# GPS_LEA5S_v_0_1.net
KiCad netlist of a schematic drawn in Altium Designer
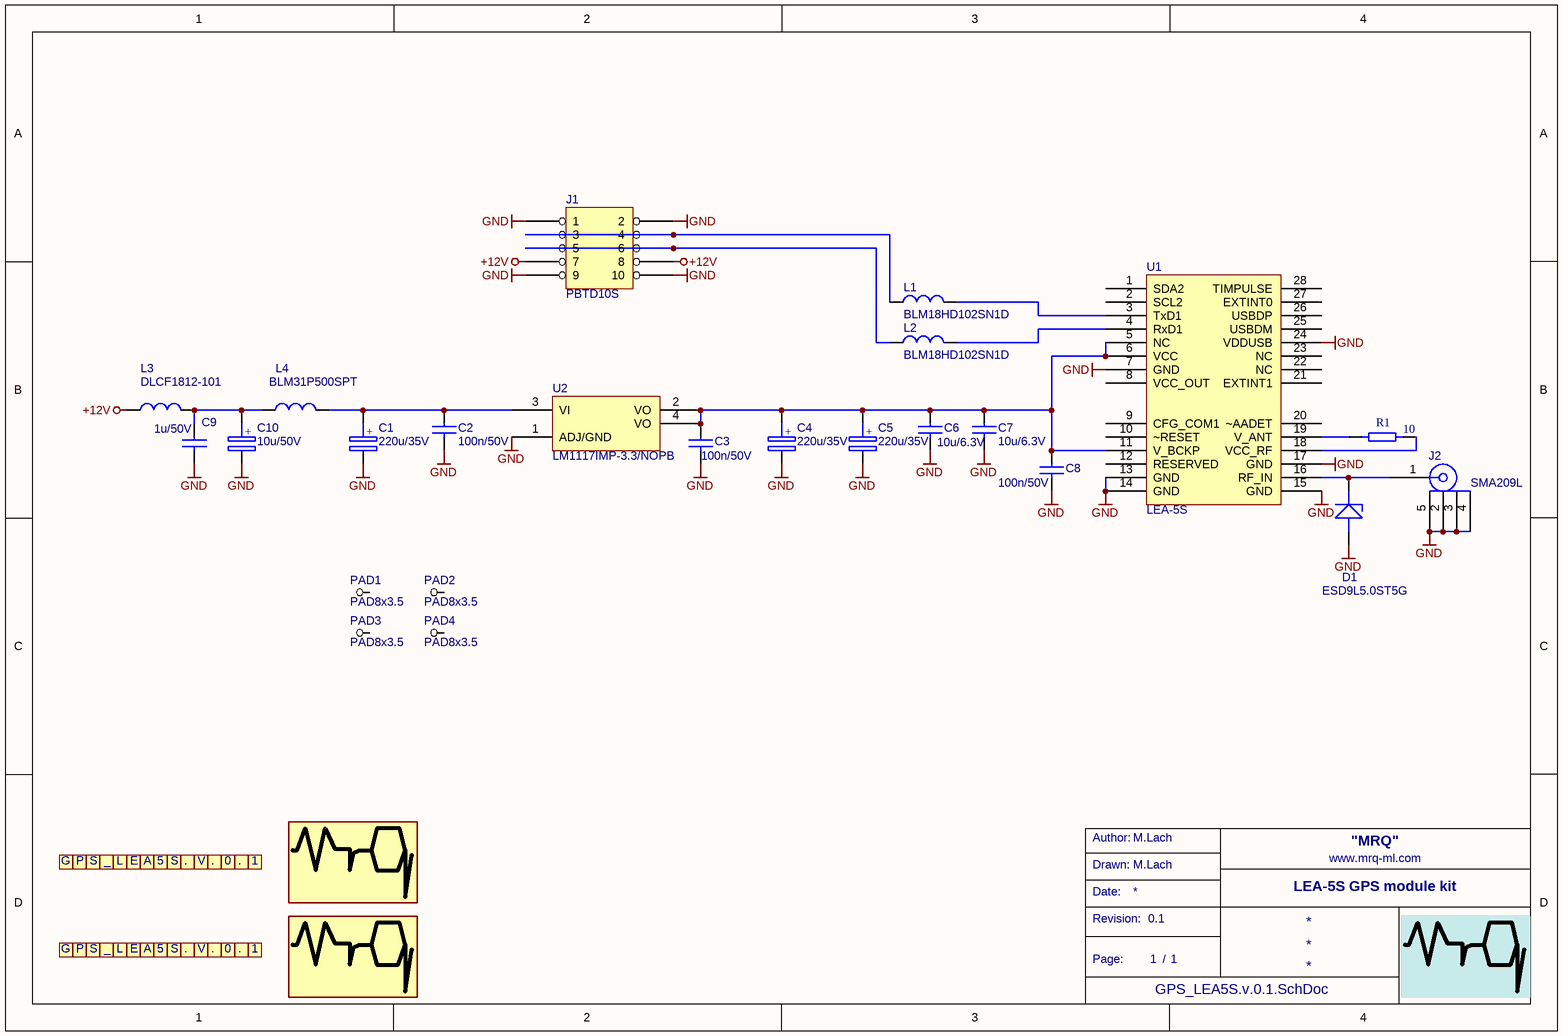
[diagram p0: GPS_LEA5S.v.0.1.SchDoc]

(export (version "E")
  (design (tool "Eeschema 10.0.6"))
  (components
    (comp (ref "C1")
      (value "220u/35V")
      (footprint "CELE")
      (fields (field (name "TOLERANCE") "20%"))
      (libsource (lib "Parts") (part "CEL"))
    )
    (comp (ref "C2")
      (value "100n/50V")
      (footprint "0805")
      (fields (field (name "TOLERANCE") "10%"))
      (libsource (lib "Parts") (part "C"))
    )
    (comp (ref "C3")
      (value "100n/50V")
      (footprint "0805")
      (fields (field (name "TOLERANCE") "10%"))
      (libsource (lib "Parts") (part "C"))
    )
    (comp (ref "C4")
      (value "220u/35V")
      (footprint "CELE")
      (fields (field (name "TOLERANCE") "20%"))
      (libsource (lib "Parts") (part "CEL"))
    )
    (comp (ref "C5")
      (value "220u/35V")
      (footprint "CELE")
      (fields (field (name "TOLERANCE") "20%"))
      (libsource (lib "Parts") (part "CEL"))
    )
    (comp (ref "C6")
      (value "10u/6.3V")
      (footprint "1206")
      (fields (field (name "TOLERANCE") "10%"))
      (libsource (lib "Parts") (part "C"))
    )
    (comp (ref "C7")
      (value "10u/6.3V")
      (footprint "1206")
      (fields (field (name "TOLERANCE") "10%"))
      (libsource (lib "Parts") (part "C"))
    )
    (comp (ref "C8")
      (value "100n/50V")
      (footprint "0805")
      (fields (field (name "TOLERANCE") "10%"))
      (libsource (lib "Parts") (part "C"))
    )
    (comp (ref "C9")
      (value "1u/50V")
      (footprint "1206")
      (fields (field (name "TOLERANCE") "10%"))
      (libsource (lib "Parts") (part "C"))
    )
    (comp (ref "C10")
      (value "10u/50V")
      (footprint "CE6.3x5.5")
      (fields (field (name "TOLERANCE") "20%"))
      (libsource (lib "Parts") (part "CEL"))
    )
    (comp (ref "D1")
      (value "ESD9L5.0ST5G")
      (footprint "SOD923")
      (libsource (lib "Parts") (part "DIODE BREAKDOWN"))
    )
    (comp (ref "J1")
      (value "PBTD10S")
      (footprint "PBTD10S")
      (description "Connector")
      (libsource (lib "Parts") (part "HEADER5X2"))
    )
    (comp (ref "J2") (value "SMA209L") (footprint "SMA209L") (libsource (lib "Parts") (part "SMA211L")))
    (comp (ref "L1") (value "BLM18HD102SN1D") (footprint "0603") (libsource (lib "Parts") (part "INDUCTOR")))
    (comp (ref "L2") (value "BLM18HD102SN1D") (footprint "0603") (libsource (lib "Parts") (part "INDUCTOR")))
    (comp (ref "L3") (value "DLCF1812-101") (footprint "1812") (libsource (lib "Parts") (part "INDUCTOR")))
    (comp (ref "L4") (value "BLM31P500SPT") (footprint "1206") (libsource (lib "Parts") (part "INDUCTOR")))
    (comp (ref "LETTER1")
      (value "LETTER_E")
      (footprint "LETTERC_E_60_10_TS")
      (libsource (lib "Schematic") (part "LETTER_E"))
    )
    (comp (ref "LETTER2")
      (value "LETTER_DOT")
      (footprint "LETTER_DOT_60_10_TS")
      (libsource (lib "Schematic") (part "LETTER_DOT"))
    )
    (comp (ref "LETTER3")
      (value "LETTER_G")
      (footprint "LETTERC_G_60_10_TS")
      (libsource (lib "Schematic") (part "LETTER_G"))
    )
    (comp (ref "LETTER4")
      (value "LETTER_DOT")
      (footprint "LETTER_DOT_60_10_TS")
      (libsource (lib "Schematic") (part "LETTER_DOT"))
    )
    (comp (ref "LETTER5")
      (value "LETTER_S")
      (footprint "LETTERC_S_60_10_TS")
      (libsource (lib "Schematic") (part "LETTER_S"))
    )
    (comp (ref "LETTER6")
      (value "LETTER_P")
      (footprint "LETTERC_P_60_10_TS")
      (libsource (lib "Schematic") (part "LETTER_P"))
    )
    (comp (ref "LETTER7")
      (value "LETTER_P")
      (footprint "LETTERC_L_60_10_TS")
      (libsource (lib "Schematic") (part "LETTER_L"))
    )
    (comp (ref "LETTER8")
      (value "LETTER_DOT")
      (footprint "LETTER_DOT_60_10_TS")
      (libsource (lib "Schematic") (part "LETTER_DOT"))
    )
    (comp (ref "LETTER9")
      (value "LETTER_1")
      (footprint "LETTER_1_60_10_TS")
      (libsource (lib "Schematic") (part "LETTER_1"))
    )
    (comp (ref "LETTER10")
      (value "LETTER_G")
      (footprint "LETTERC_G_60_10_TS")
      (libsource (lib "Schematic") (part "LETTER_G"))
    )
    (comp (ref "LETTER11")
      (value "LETTER_UNDERSCORE")
      (footprint "LETTER_UNDERSCORE_60_10_TS")
      (libsource (lib "Schematic") (part "LETTER_UNDERSCORE"))
    )
    (comp (ref "LETTER12")
      (value "LETTER_A_CAPITAL")
      (footprint "LETTERC_A_60_10_TS")
      (libsource (lib "Schematic") (part "LETTER_A"))
    )
    (comp (ref "LETTER13")
      (value "LETTER_5")
      (footprint "LETTER_5_60_10_TS")
      (libsource (lib "Schematic") (part "LETTER_5"))
    )
    (comp (ref "LETTER14")
      (value "LETTER_S")
      (footprint "LETTERC_S_60_10_TS")
      (libsource (lib "Schematic") (part "LETTER_S"))
    )
    (comp (ref "LETTER15")
      (value "LETTER_P")
      (footprint "LETTERC_P_60_10_TS")
      (libsource (lib "Schematic") (part "LETTER_P"))
    )
    (comp (ref "LETTER16")
      (value "LETTER_V")
      (footprint "LETTER_V_60_10_TS")
      (libsource (lib "Schematic") (part "LETTER_V"))
    )
    (comp (ref "LETTER17")
      (value "LETTER_S")
      (footprint "LETTERC_S_60_10_TS")
      (libsource (lib "Schematic") (part "LETTER_S"))
    )
    (comp (ref "LETTER18")
      (value "LETTER_0")
      (footprint "LETTER_0_60_10_TS")
      (libsource (lib "Schematic") (part "LETTER_0"))
    )
    (comp (ref "LETTER19")
      (value "LETTER_UNDERSCORE")
      (footprint "LETTER_UNDERSCORE_60_10_TS")
      (libsource (lib "Schematic") (part "LETTER_UNDERSCORE"))
    )
    (comp (ref "LETTER20")
      (value "LETTER_P")
      (footprint "LETTERC_L_60_10_TS")
      (libsource (lib "Schematic") (part "LETTER_L"))
    )
    (comp (ref "LETTER21")
      (value "LETTER_E")
      (footprint "LETTERC_E_60_10_TS")
      (libsource (lib "Schematic") (part "LETTER_E"))
    )
    (comp (ref "LETTER22")
      (value "LETTER_A_CAPITAL")
      (footprint "LETTERC_A_60_10_TS")
      (libsource (lib "Schematic") (part "LETTER_A"))
    )
    (comp (ref "LETTER23")
      (value "LETTER_5")
      (footprint "LETTER_5_60_10_TS")
      (libsource (lib "Schematic") (part "LETTER_5"))
    )
    (comp (ref "LETTER24")
      (value "LETTER_S")
      (footprint "LETTERC_S_60_10_TS")
      (libsource (lib "Schematic") (part "LETTER_S"))
    )
    (comp (ref "LETTER25")
      (value "LETTER_DOT")
      (footprint "LETTER_DOT_60_10_TS")
      (libsource (lib "Schematic") (part "LETTER_DOT"))
    )
    (comp (ref "LETTER26")
      (value "LETTER_V")
      (footprint "LETTER_V_60_10_TS")
      (libsource (lib "Schematic") (part "LETTER_V"))
    )
    (comp (ref "LETTER27")
      (value "LETTER_DOT")
      (footprint "LETTER_DOT_60_10_TS")
      (libsource (lib "Schematic") (part "LETTER_DOT"))
    )
    (comp (ref "LETTER28")
      (value "LETTER_0")
      (footprint "LETTER_0_60_10_TS")
      (libsource (lib "Schematic") (part "LETTER_0"))
    )
    (comp (ref "LETTER29")
      (value "LETTER_DOT")
      (footprint "LETTER_DOT_60_10_TS")
      (libsource (lib "Schematic") (part "LETTER_DOT"))
    )
    (comp (ref "LETTER30")
      (value "LETTER_1")
      (footprint "LETTER_1_60_10_TS")
      (libsource (lib "Schematic") (part "LETTER_1"))
    )
    (comp (ref "LOGO1")
      (value "MRQLOGO")
      (footprint "MRQ_5_TS")
      (libsource (lib "Schematic") (part "MRQLOGO"))
    )
    (comp (ref "LOGO3")
      (value "MRQLOGO")
      (footprint "MRQ_5_TS")
      (libsource (lib "Schematic") (part "MRQLOGO"))
    )
    (comp (ref "PAD1")
      (value "PAD8x3.5")
      (footprint "PAD8x3.5")
      (libsource (lib "Schematic") (part "PAD8x3.5"))
    )
    (comp (ref "PAD2")
      (value "PAD8x3.5")
      (footprint "PAD8x3.5")
      (libsource (lib "Schematic") (part "PAD8x3.5"))
    )
    (comp (ref "PAD3")
      (value "PAD8x3.5")
      (footprint "PAD8x3.5")
      (libsource (lib "Schematic") (part "PAD8x3.5"))
    )
    (comp (ref "PAD4")
      (value "PAD8x3.5")
      (footprint "PAD8x3.5")
      (libsource (lib "Schematic") (part "PAD8x3.5"))
    )
    (comp (ref "R1")
      (value "10")
      (footprint "0805")
      (fields (field (name "TOLERANCE") "5%"))
      (libsource (lib "Parts") (part "R"))
    )
    (comp (ref "TB") (value "TITLEBLOCK") (libsource (lib "Schematic") (part "TITLEBLOCK")))
    (comp (ref "U1") (value "LEA-5S") (footprint "LEA-LA") (libsource (lib "Parts") (part "LEA-5S")))
    (comp (ref "U2")
      (value "LM1117IMP-3.3/NOPB")
      (footprint "SOT-223")
      (libsource (lib "Parts") (part "LM1117IMP"))
    )
  )
  (nets
    (net (code "1") (name "+12V") (class "Default")
      (node (ref "J1") (pin "7") (pinfunction "7_7") (pintype "passive"))
      (node (ref "J1") (pin "8") (pinfunction "8_8") (pintype "passive"))
      (node (ref "L3") (pin "1") (pinfunction "1_1") (pintype "passive"))
    )
    (net (code "2") (name "GND") (class "Default")
      (node (ref "C1") (pin "1") (pinfunction "1_1") (pintype "passive"))
      (node (ref "C10") (pin "1") (pinfunction "1_1") (pintype "passive"))
      (node (ref "C2") (pin "2") (pinfunction "2_2") (pintype "passive"))
      (node (ref "C3") (pin "2") (pinfunction "2_2") (pintype "passive"))
      (node (ref "C4") (pin "1") (pinfunction "1_1") (pintype "passive"))
      (node (ref "C5") (pin "1") (pinfunction "1_1") (pintype "passive"))
      (node (ref "C6") (pin "2") (pinfunction "2_2") (pintype "passive"))
      (node (ref "C7") (pin "2") (pinfunction "2_2") (pintype "passive"))
      (node (ref "C8") (pin "2") (pinfunction "2_2") (pintype "passive"))
      (node (ref "C9") (pin "2") (pinfunction "2_2") (pintype "passive"))
      (node (ref "D1") (pin "ANOD") (pinfunction "ANOD_ANOD") (pintype "passive"))
      (node (ref "J1") (pin "1") (pinfunction "1_1") (pintype "passive"))
      (node (ref "J1") (pin "10") (pinfunction "10_10") (pintype "passive"))
      (node (ref "J1") (pin "2") (pinfunction "2_2") (pintype "passive"))
      (node (ref "J1") (pin "9") (pinfunction "9_9") (pintype "passive"))
      (node (ref "J2") (pin "2") (pinfunction "2_2") (pintype "passive"))
      (node (ref "J2") (pin "3") (pinfunction "3_3") (pintype "passive"))
      (node (ref "J2") (pin "4") (pinfunction "4_4") (pintype "passive"))
      (node (ref "J2") (pin "5") (pinfunction "5_5") (pintype "passive"))
      (node (ref "U1") (pin "13") (pinfunction "GND_13") (pintype "passive"))
      (node (ref "U1") (pin "14") (pinfunction "GND_14") (pintype "passive"))
      (node (ref "U1") (pin "15") (pinfunction "GND_15") (pintype "passive"))
      (node (ref "U1") (pin "17") (pinfunction "GND_17") (pintype "passive"))
      (node (ref "U1") (pin "24") (pinfunction "VDDUSB_24") (pintype "passive"))
      (node (ref "U1") (pin "7") (pinfunction "GND_7") (pintype "passive"))
      (node (ref "U2") (pin "1") (pinfunction "ADJ/GND_1") (pintype "passive"))
    )
    (net (code "3") (name "Net-(C10-Pad2)") (class "Default")
      (node (ref "C10") (pin "2") (pinfunction "2_2") (pintype "passive"))
      (node (ref "C9") (pin "1") (pinfunction "1_1") (pintype "passive"))
      (node (ref "L3") (pin "2") (pinfunction "2_2") (pintype "passive"))
      (node (ref "L4") (pin "1") (pinfunction "1_1") (pintype "passive"))
    )
    (net (code "4") (name "Net-(J1-Pad3)") (class "Default")
      (node (ref "J1") (pin "3") (pinfunction "3_3") (pintype "passive"))
      (node (ref "J1") (pin "4") (pinfunction "4_4") (pintype "passive"))
      (node (ref "L1") (pin "1") (pinfunction "1_1") (pintype "passive"))
    )
    (net (code "5") (name "Net-(J1-Pad5)") (class "Default")
      (node (ref "J1") (pin "5") (pinfunction "5_5") (pintype "passive"))
      (node (ref "J1") (pin "6") (pinfunction "6_6") (pintype "passive"))
      (node (ref "L2") (pin "1") (pinfunction "1_1") (pintype "passive"))
    )
    (net (code "6") (name "Net-(U1-RF_IN)") (class "Default")
      (node (ref "D1") (pin "CATH") (pinfunction "CATH_CATH") (pintype "passive"))
      (node (ref "J2") (pin "1") (pinfunction "1_1") (pintype "passive"))
      (node (ref "U1") (pin "16") (pinfunction "RF_IN_16") (pintype "passive"))
    )
    (net (code "7") (name "Net-(U1-RxD1)") (class "Default")
      (node (ref "L2") (pin "2") (pinfunction "2_2") (pintype "passive"))
      (node (ref "U1") (pin "4") (pinfunction "RxD1_4") (pintype "passive"))
    )
    (net (code "8") (name "Net-(U1-TxD1)") (class "Default")
      (node (ref "L1") (pin "2") (pinfunction "2_2") (pintype "passive"))
      (node (ref "U1") (pin "3") (pinfunction "TxD1_3") (pintype "passive"))
    )
    (net (code "9") (name "Net-(U1-VCC)") (class "Default")
      (node (ref "C3") (pin "1") (pinfunction "1_1") (pintype "passive"))
      (node (ref "C4") (pin "2") (pinfunction "2_2") (pintype "passive"))
      (node (ref "C5") (pin "2") (pinfunction "2_2") (pintype "passive"))
      (node (ref "C6") (pin "1") (pinfunction "1_1") (pintype "passive"))
      (node (ref "C7") (pin "1") (pinfunction "1_1") (pintype "passive"))
      (node (ref "C8") (pin "1") (pinfunction "1_1") (pintype "passive"))
      (node (ref "U1") (pin "11") (pinfunction "V_BCKP_11") (pintype "passive"))
      (node (ref "U1") (pin "5") (pinfunction "NC_5") (pintype "passive"))
      (node (ref "U1") (pin "6") (pinfunction "VCC_6") (pintype "passive"))
      (node (ref "U2") (pin "2") (pinfunction "VO_2") (pintype "passive"))
      (node (ref "U2") (pin "4") (pinfunction "VO_4") (pintype "passive"))
    )
    (net (code "10") (name "Net-(U1-VCC_RF)") (class "Default")
      (node (ref "R1") (pin "2") (pinfunction "2_2") (pintype "passive"))
      (node (ref "U1") (pin "18") (pinfunction "VCC_RF_18") (pintype "passive"))
    )
    (net (code "11") (name "Net-(U1-V_ANT)") (class "Default")
      (node (ref "R1") (pin "1") (pinfunction "1_1") (pintype "passive"))
      (node (ref "U1") (pin "19") (pinfunction "V_ANT_19") (pintype "passive"))
    )
    (net (code "12") (name "Net-(U2-VI)") (class "Default")
      (node (ref "C1") (pin "2") (pinfunction "2_2") (pintype "passive"))
      (node (ref "C2") (pin "1") (pinfunction "1_1") (pintype "passive"))
      (node (ref "L4") (pin "2") (pinfunction "2_2") (pintype "passive"))
      (node (ref "U2") (pin "3") (pinfunction "VI_3") (pintype "passive"))
    )
    (net (code "13") (name "unconnected-(PAD1-Pad1)") (class "Default")
      (node (ref "PAD1") (pin "1") (pinfunction "1_1") (pintype "passive"))
    )
    (net (code "14") (name "unconnected-(PAD2-Pad1)") (class "Default")
      (node (ref "PAD2") (pin "1") (pinfunction "1_1") (pintype "passive"))
    )
    (net (code "15") (name "unconnected-(PAD3-Pad1)") (class "Default")
      (node (ref "PAD3") (pin "1") (pinfunction "1_1") (pintype "passive"))
    )
    (net (code "16") (name "unconnected-(PAD4-Pad1)") (class "Default")
      (node (ref "PAD4") (pin "1") (pinfunction "1_1") (pintype "passive"))
    )
    (net (code "17") (name "unconnected-(U1-CFG_COM1-Pad9)") (class "Default")
      (node (ref "U1") (pin "9") (pinfunction "CFG_COM1_9") (pintype "passive"))
    )
    (net (code "18") (name "unconnected-(U1-EXTINT0-Pad27)") (class "Default")
      (node (ref "U1") (pin "27") (pinfunction "EXTINT0_27") (pintype "passive"))
    )
    (net (code "19") (name "unconnected-(U1-EXTINT1-Pad21)") (class "Default")
      (node (ref "U1") (pin "21") (pinfunction "EXTINT1_21") (pintype "passive"))
    )
    (net (code "20") (name "unconnected-(U1-NC-Pad22)") (class "Default")
      (node (ref "U1") (pin "22") (pinfunction "NC_22") (pintype "passive"))
    )
    (net (code "21") (name "unconnected-(U1-NC-Pad23)") (class "Default")
      (node (ref "U1") (pin "23") (pinfunction "NC_23") (pintype "passive"))
    )
    (net (code "22") (name "unconnected-(U1-RESERVED-Pad12)") (class "Default")
      (node (ref "U1") (pin "12") (pinfunction "RESERVED_12") (pintype "passive"))
    )
    (net (code "23") (name "unconnected-(U1-SCL2-Pad2)") (class "Default")
      (node (ref "U1") (pin "2") (pinfunction "SCL2_2") (pintype "passive"))
    )
    (net (code "24") (name "unconnected-(U1-SDA2-Pad1)") (class "Default")
      (node (ref "U1") (pin "1") (pinfunction "SDA2_1") (pintype "passive"))
    )
    (net (code "25") (name "unconnected-(U1-TIMPULSE-Pad28)") (class "Default")
      (node (ref "U1") (pin "28") (pinfunction "TIMPULSE_28") (pintype "passive"))
    )
    (net (code "26") (name "unconnected-(U1-USBDM-Pad25)") (class "Default")
      (node (ref "U1") (pin "25") (pinfunction "USBDM_25") (pintype "passive"))
    )
    (net (code "27") (name "unconnected-(U1-USBDP-Pad26)") (class "Default")
      (node (ref "U1") (pin "26") (pinfunction "USBDP_26") (pintype "passive"))
    )
    (net (code "28") (name "unconnected-(U1-VCC_OUT-Pad8)") (class "Default")
      (node (ref "U1") (pin "8") (pinfunction "VCC_OUT_8") (pintype "passive"))
    )
    (net (code "29") (name "unconnected-(U1-~AADET-Pad20)") (class "Default")
      (node (ref "U1") (pin "20") (pinfunction "~AADET_20") (pintype "passive"))
    )
    (net (code "30") (name "unconnected-(U1-~RESET-Pad10)") (class "Default")
      (node (ref "U1") (pin "10") (pinfunction "~RESET_10") (pintype "passive"))
    )
  )
)
